# pic10_prog_breakout.net
KiCad netlist of a schematic drawn in EAGLE
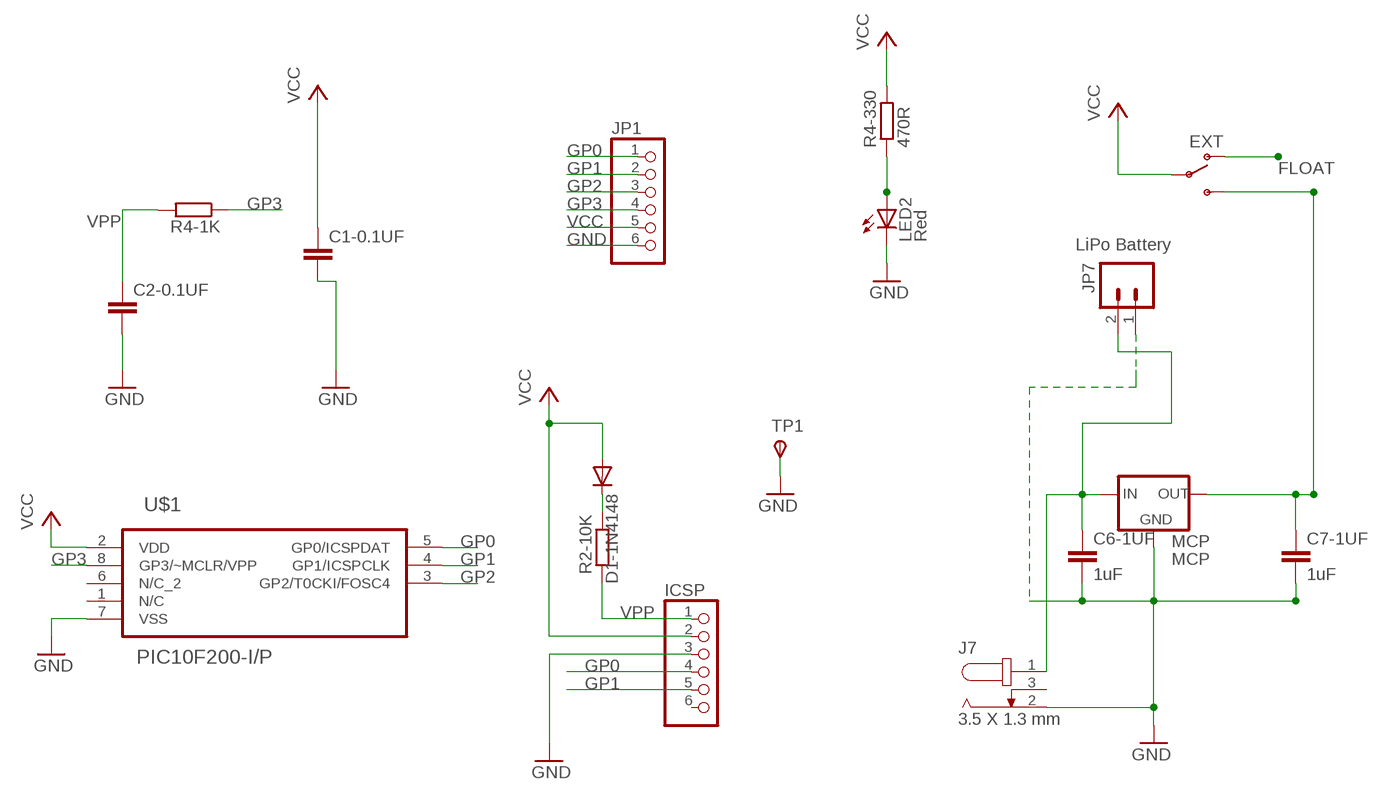
[diagram p0: schematic, sheet 1]

(export (version "E")
  (design (tool "Eeschema 10.0.6"))
  (components
    (comp (ref "C1-0.1UF")
      (value "C-EU025-025X050")
      (footprint "eagle-import:C025-025X050")
      (libsource (lib "eagle-import") (part "C-EU025-025X050"))
    )
    (comp (ref "C2-0.1UF")
      (value "C-EU025-025X050")
      (footprint "eagle-import:C025-025X050")
      (libsource (lib "eagle-import") (part "C-EU025-025X050"))
    )
    (comp (ref "C6-1UF")
      (value "1uF")
      (footprint "eagle-import:C050-025X075")
      (libsource (lib "eagle-import") (part "C-EU050-025X075"))
    )
    (comp (ref "C7-1UF")
      (value "1uF")
      (footprint "eagle-import:C050-025X075")
      (libsource (lib "eagle-import") (part "C-EU050-025X075"))
    )
    (comp (ref "D1-1N4148")
      (value "1N4148")
      (footprint "eagle-import:DO35-7")
      (libsource (lib "eagle-import") (part "1N4148DO35-7"))
    )
    (comp (ref "ICSP")
      (value "PINHD-1X6")
      (footprint "eagle-import:1X06")
      (libsource (lib "eagle-import") (part "PINHD-1X6"))
    )
    (comp (ref "J7")
      (value "3.5 X 1.3 mm")
      (footprint "eagle-import:3.5X1.3MM_DC_JACK")
      (libsource (lib "eagle-import") (part "DC_JACK_3.5X1.3MM"))
    )
    (comp (ref "JP1")
      (value "PINHD-1X6")
      (footprint "eagle-import:1X06")
      (libsource (lib "eagle-import") (part "PINHD-1X6"))
    )
    (comp (ref "JP7")
      (value "LiPo Battery")
      (footprint "eagle-import:JST-2-PTH")
      (libsource (lib "eagle-import") (part "M02JST-PTH-2"))
    )
    (comp (ref "LED2")
      (value "Red")
      (footprint "eagle-import:LED3MM")
      (libsource (lib "eagle-import") (part "LED3MM"))
    )
    (comp (ref "MCP")
      (value "MCP")
      (footprint "eagle-import:TO92-")
      (libsource (lib "eagle-import") (part "MCP1700TO-92"))
    )
    (comp (ref "ON")
      (value "EXT")
      (footprint "eagle-import:SWITCH-SPDT")
      (libsource (lib "eagle-import") (part "SWITCH-SPSTPTH"))
    )
    (comp (ref "R2-10K")
      (value "R-EU_0207/10")
      (footprint "eagle-import:0207_10")
      (libsource (lib "eagle-import") (part "R-EU_0207/10"))
    )
    (comp (ref "R4-1K")
      (value "R-EU_0207/10")
      (footprint "eagle-import:0207_10")
      (libsource (lib "eagle-import") (part "R-EU_0207/10"))
    )
    (comp (ref "R4-330")
      (value "470R")
      (footprint "eagle-import:0207_10")
      (libsource (lib "eagle-import") (part "R-EU_0207/10"))
    )
    (comp (ref "TP1")
      (value "TPSTP20R")
      (footprint "eagle-import:TP20R")
      (libsource (lib "eagle-import") (part "TPSTP20R"))
    )
    (comp (ref "U$1")
      (value "PIC10F200-I/P")
      (footprint "eagle-import:DIP254P762X533-8")
      (libsource (lib "eagle-import") (part "PIC10F200-I/P"))
    )
  )
  (nets
    (net (code "1") (name "/FLOAT") (class "Default")
      (node (ref "ON") (pin "1") (pinfunction "O_1") (pintype "passive"))
    )
    (net (code "2") (name "/GP0") (class "Default")
      (node (ref "ICSP") (pin "4") (pinfunction "4_4") (pintype "passive"))
      (node (ref "JP1") (pin "1") (pinfunction "1_1") (pintype "passive"))
      (node (ref "U$1") (pin "5") (pinfunction "GP0/ICSPDAT_5") (pintype "bidirectional"))
    )
    (net (code "3") (name "/GP1") (class "Default")
      (node (ref "ICSP") (pin "5") (pinfunction "5_5") (pintype "passive"))
      (node (ref "JP1") (pin "2") (pinfunction "2_2") (pintype "passive"))
      (node (ref "U$1") (pin "4") (pinfunction "GP1/ICSPCLK_4") (pintype "bidirectional"))
    )
    (net (code "4") (name "/GP2") (class "Default")
      (node (ref "JP1") (pin "3") (pinfunction "3_3") (pintype "passive"))
      (node (ref "U$1") (pin "3") (pinfunction "GP2/T0CKI/FOSC4_3") (pintype "bidirectional"))
    )
    (net (code "5") (name "/GP3") (class "Default")
      (node (ref "JP1") (pin "4") (pinfunction "4_4") (pintype "passive"))
      (node (ref "R4-1K") (pin "1") (pinfunction "1_1") (pintype "passive"))
      (node (ref "U$1") (pin "8") (pinfunction "GP3/~{MCLR/VPP}_8") (pintype "input"))
    )
    (net (code "6") (name "/VPP") (class "Default")
      (node (ref "C2-0.1UF") (pin "1") (pinfunction "1_1") (pintype "passive"))
      (node (ref "ICSP") (pin "1") (pinfunction "1_1") (pintype "passive"))
      (node (ref "R2-10K") (pin "1") (pinfunction "1_1") (pintype "passive"))
      (node (ref "R4-1K") (pin "2") (pinfunction "2_2") (pintype "passive"))
    )
    (net (code "7") (name "GND") (class "Default")
      (node (ref "C1-0.1UF") (pin "2") (pinfunction "2_2") (pintype "passive"))
      (node (ref "C2-0.1UF") (pin "2") (pinfunction "2_2") (pintype "passive"))
      (node (ref "C6-1UF") (pin "2") (pinfunction "2_2") (pintype "passive"))
      (node (ref "C7-1UF") (pin "2") (pinfunction "2_2") (pintype "passive"))
      (node (ref "ICSP") (pin "3") (pinfunction "3_3") (pintype "passive"))
      (node (ref "J7") (pin "2") (pinfunction "2_2") (pintype "passive"))
      (node (ref "JP1") (pin "6") (pinfunction "6_6") (pintype "passive"))
      (node (ref "JP7") (pin "1") (pinfunction "1_1") (pintype "passive"))
      (node (ref "LED2") (pin "K") (pinfunction "C_K") (pintype "passive"))
      (node (ref "MCP") (pin "3") (pinfunction "GND_3") (pintype "input"))
      (node (ref "TP1") (pin "TP") (pinfunction "PP_TP") (pintype "input"))
      (node (ref "U$1") (pin "7") (pinfunction "VSS_7") (pintype "power_in"))
    )
    (net (code "8") (name "Net-(D1-1N4148-PadC)") (class "Default")
      (node (ref "D1-1N4148") (pin "C") (pinfunction "C_C") (pintype "passive"))
      (node (ref "R2-10K") (pin "2") (pinfunction "2_2") (pintype "passive"))
    )
    (net (code "9") (name "Net-(LED2-PadA)") (class "Default")
      (node (ref "LED2") (pin "A") (pinfunction "A_A") (pintype "passive"))
      (node (ref "R4-330") (pin "1") (pinfunction "1_1") (pintype "passive"))
    )
    (net (code "10") (name "Net-(MCP-IN)") (class "Default")
      (node (ref "C6-1UF") (pin "1") (pinfunction "1_1") (pintype "passive"))
      (node (ref "J7") (pin "1") (pinfunction "1_1") (pintype "passive"))
      (node (ref "JP7") (pin "2") (pinfunction "2_2") (pintype "passive"))
      (node (ref "MCP") (pin "2") (pinfunction "IN_2") (pintype "input"))
    )
    (net (code "11") (name "Net-(MCP-OUT)") (class "Default")
      (node (ref "C7-1UF") (pin "1") (pinfunction "1_1") (pintype "passive"))
      (node (ref "MCP") (pin "1") (pinfunction "OUT_1") (pintype "passive"))
      (node (ref "ON") (pin "3") (pinfunction "S_3") (pintype "passive"))
    )
    (net (code "12") (name "VCC") (class "Default")
      (node (ref "C1-0.1UF") (pin "1") (pinfunction "1_1") (pintype "passive"))
      (node (ref "D1-1N4148") (pin "A") (pinfunction "A_A") (pintype "passive"))
      (node (ref "ICSP") (pin "2") (pinfunction "2_2") (pintype "passive"))
      (node (ref "JP1") (pin "5") (pinfunction "5_5") (pintype "passive"))
      (node (ref "ON") (pin "2") (pinfunction "P_2") (pintype "passive"))
      (node (ref "R4-330") (pin "2") (pinfunction "2_2") (pintype "passive"))
      (node (ref "U$1") (pin "2") (pinfunction "VDD_2") (pintype "power_in"))
    )
    (net (code "13") (name "unconnected-(ICSP-Pad6)") (class "Default")
      (node (ref "ICSP") (pin "6") (pinfunction "6_6") (pintype "passive"))
    )
    (net (code "14") (name "unconnected-(J7-Pad3)") (class "Default")
      (node (ref "J7") (pin "3") (pinfunction "3_3") (pintype "passive"))
    )
    (net (code "15") (name "unconnected-(U$1-N{slash}C-Pad1)") (class "Default")
      (node (ref "U$1") (pin "1") (pinfunction "N/C_1") (pintype "no_connect"))
    )
    (net (code "16") (name "unconnected-(U$1-N{slash}C_2-Pad6)") (class "Default")
      (node (ref "U$1") (pin "6") (pinfunction "N/C_2_6") (pintype "no_connect"))
    )
  )
)
